# budapest_rev_A.net
KiCad netlist of a schematic drawn in EAGLE
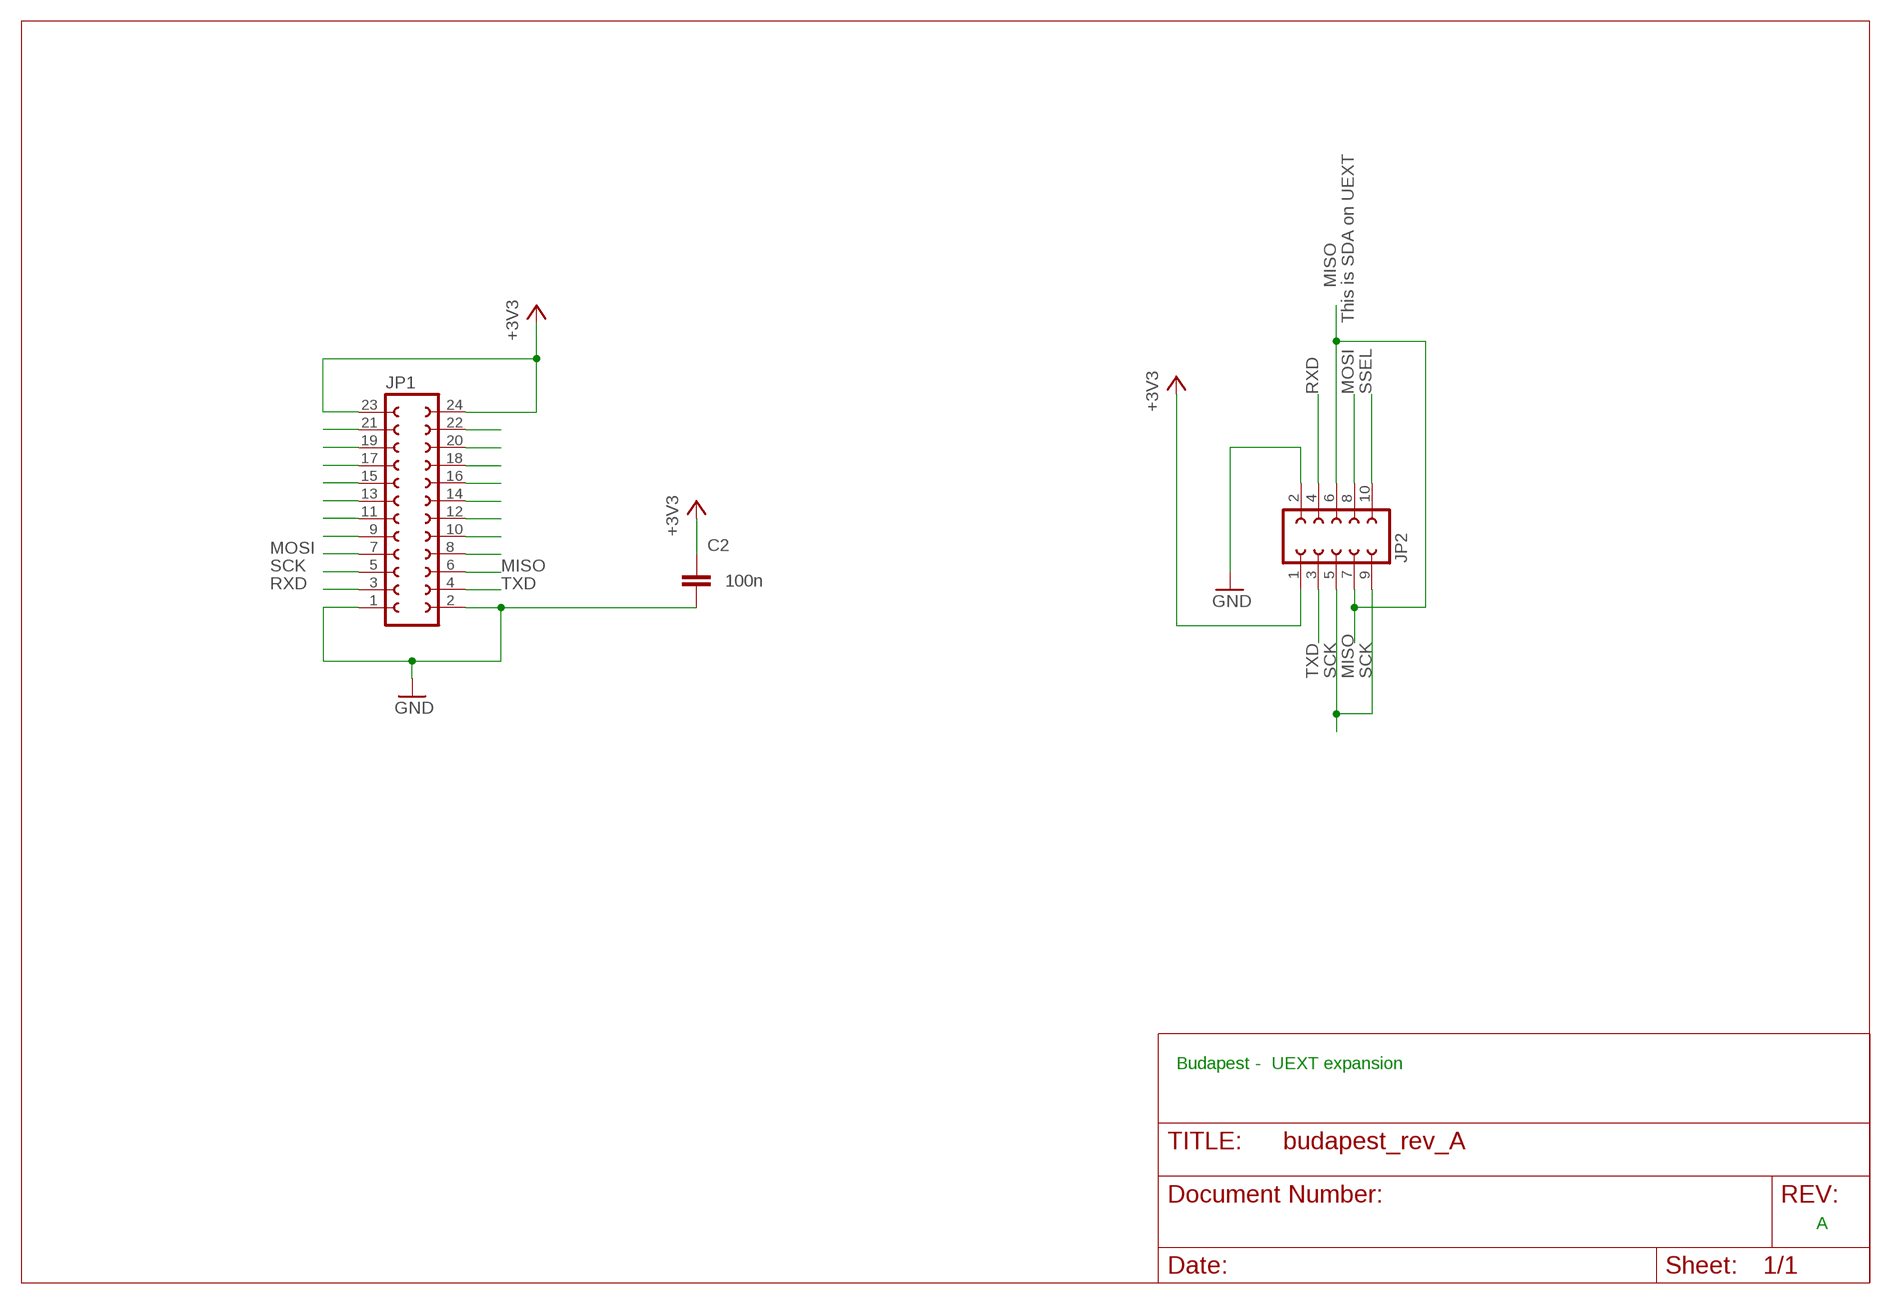
[diagram p0: schematic, sheet 1]

(export (version "E")
  (design (tool "Eeschema 10.0.6"))
  (components
    (comp (ref "C2")
      (value "100n")
      (footprint "eagle-import:C0805")
      (libsource (lib "eagle-import") (part "C-EUC0805"))
    )
    (comp (ref "JP1")
      (value "FE12-2")
      (footprint "eagle-import:FE12-2")
      (libsource (lib "eagle-import") (part "FE12-2"))
    )
    (comp (ref "JP2")
      (value "FE05-2")
      (footprint "eagle-import:FE05-2")
      (libsource (lib "eagle-import") (part "FE05-2"))
    )
  )
  (nets
    (net (code "1") (name "+3V3") (class "Default")
      (node (ref "C2") (pin "1") (pinfunction "1_1") (pintype "passive"))
      (node (ref "JP1") (pin "23") (pinfunction "23_23") (pintype "passive"))
      (node (ref "JP1") (pin "24") (pinfunction "24_24") (pintype "passive"))
      (node (ref "JP2") (pin "1") (pinfunction "1_1") (pintype "passive"))
    )
    (net (code "2") (name "/MISO") (class "Default")
      (node (ref "JP1") (pin "6") (pinfunction "6_6") (pintype "passive"))
      (node (ref "JP2") (pin "6") (pinfunction "6_6") (pintype "passive"))
      (node (ref "JP2") (pin "7") (pinfunction "7_7") (pintype "passive"))
    )
    (net (code "3") (name "/MOSI") (class "Default")
      (node (ref "JP1") (pin "7") (pinfunction "7_7") (pintype "passive"))
      (node (ref "JP2") (pin "8") (pinfunction "8_8") (pintype "passive"))
    )
    (net (code "4") (name "/RXD") (class "Default")
      (node (ref "JP1") (pin "3") (pinfunction "3_3") (pintype "passive"))
      (node (ref "JP2") (pin "4") (pinfunction "4_4") (pintype "passive"))
    )
    (net (code "5") (name "/SCK") (class "Default")
      (node (ref "JP1") (pin "5") (pinfunction "5_5") (pintype "passive"))
      (node (ref "JP2") (pin "5") (pinfunction "5_5") (pintype "passive"))
      (node (ref "JP2") (pin "9") (pinfunction "9_9") (pintype "passive"))
    )
    (net (code "6") (name "/SSEL") (class "Default")
      (node (ref "JP2") (pin "10") (pinfunction "10_10") (pintype "passive"))
    )
    (net (code "7") (name "/TXD") (class "Default")
      (node (ref "JP1") (pin "4") (pinfunction "4_4") (pintype "passive"))
      (node (ref "JP2") (pin "3") (pinfunction "3_3") (pintype "passive"))
    )
    (net (code "8") (name "GND") (class "Default")
      (node (ref "C2") (pin "2") (pinfunction "2_2") (pintype "passive"))
      (node (ref "JP1") (pin "1") (pinfunction "1_1") (pintype "passive"))
      (node (ref "JP1") (pin "2") (pinfunction "2_2") (pintype "passive"))
      (node (ref "JP2") (pin "2") (pinfunction "2_2") (pintype "passive"))
    )
    (net (code "9") (name "unconnected-(JP1-Pad8)") (class "Default")
      (node (ref "JP1") (pin "8") (pinfunction "8_8") (pintype "passive"))
    )
    (net (code "10") (name "unconnected-(JP1-Pad9)") (class "Default")
      (node (ref "JP1") (pin "9") (pinfunction "9_9") (pintype "passive"))
    )
    (net (code "11") (name "unconnected-(JP1-Pad10)") (class "Default")
      (node (ref "JP1") (pin "10") (pinfunction "10_10") (pintype "passive"))
    )
    (net (code "12") (name "unconnected-(JP1-Pad11)") (class "Default")
      (node (ref "JP1") (pin "11") (pinfunction "11_11") (pintype "passive"))
    )
    (net (code "13") (name "unconnected-(JP1-Pad12)") (class "Default")
      (node (ref "JP1") (pin "12") (pinfunction "12_12") (pintype "passive"))
    )
    (net (code "14") (name "unconnected-(JP1-Pad13)") (class "Default")
      (node (ref "JP1") (pin "13") (pinfunction "13_13") (pintype "passive"))
    )
    (net (code "15") (name "unconnected-(JP1-Pad14)") (class "Default")
      (node (ref "JP1") (pin "14") (pinfunction "14_14") (pintype "passive"))
    )
    (net (code "16") (name "unconnected-(JP1-Pad15)") (class "Default")
      (node (ref "JP1") (pin "15") (pinfunction "15_15") (pintype "passive"))
    )
    (net (code "17") (name "unconnected-(JP1-Pad16)") (class "Default")
      (node (ref "JP1") (pin "16") (pinfunction "16_16") (pintype "passive"))
    )
    (net (code "18") (name "unconnected-(JP1-Pad17)") (class "Default")
      (node (ref "JP1") (pin "17") (pinfunction "17_17") (pintype "passive"))
    )
    (net (code "19") (name "unconnected-(JP1-Pad18)") (class "Default")
      (node (ref "JP1") (pin "18") (pinfunction "18_18") (pintype "passive"))
    )
    (net (code "20") (name "unconnected-(JP1-Pad19)") (class "Default")
      (node (ref "JP1") (pin "19") (pinfunction "19_19") (pintype "passive"))
    )
    (net (code "21") (name "unconnected-(JP1-Pad20)") (class "Default")
      (node (ref "JP1") (pin "20") (pinfunction "20_20") (pintype "passive"))
    )
    (net (code "22") (name "unconnected-(JP1-Pad21)") (class "Default")
      (node (ref "JP1") (pin "21") (pinfunction "21_21") (pintype "passive"))
    )
    (net (code "23") (name "unconnected-(JP1-Pad22)") (class "Default")
      (node (ref "JP1") (pin "22") (pinfunction "22_22") (pintype "passive"))
    )
  )
)
